# OpenMoteSTM-Border_DP83848CVV.net
KiCad netlist of a schematic drawn in Altium Designer
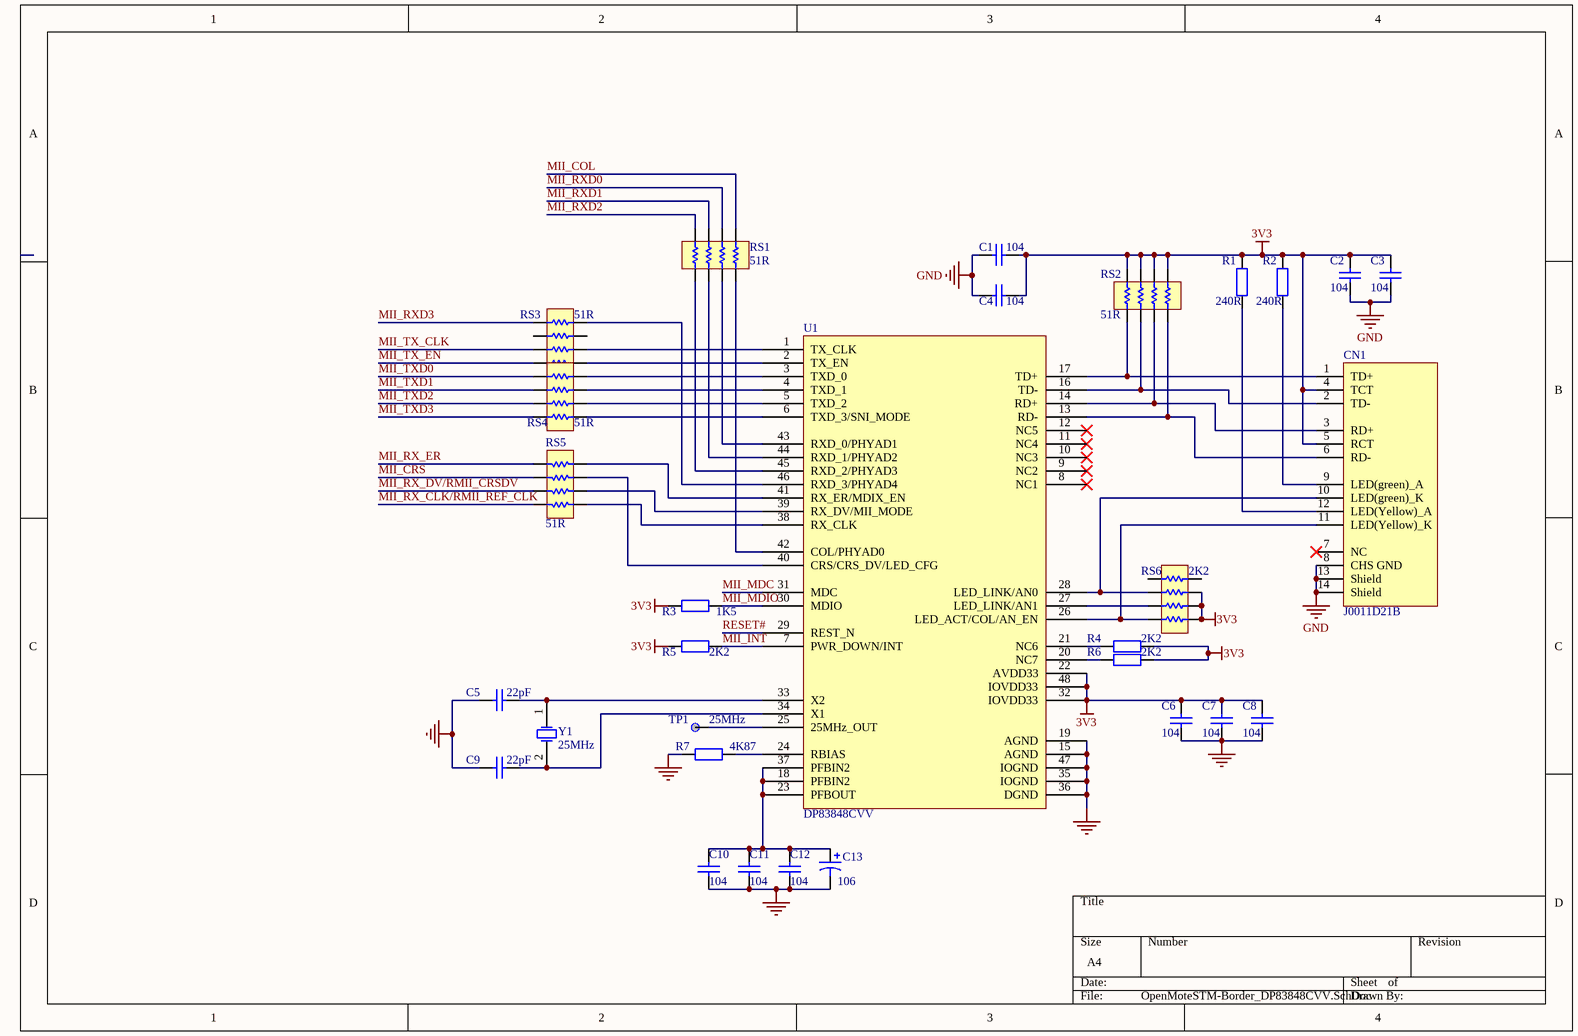
[diagram p0: OpenMoteSTM-Border_DP83848CVV.SchDoc]

(export (version "E")
  (design (tool "Eeschema 10.0.6"))
  (components
    (comp (ref "C1")
      (value "104")
      (footprint "0603")
      (description "Capacitor")
      (fields (field (name "Comment") "Cap") (field (name "PUBLISHER") "Altium Limited"))
      (libsource (lib "Miscellaneous Devices") (part "Cap"))
    )
    (comp (ref "C2")
      (value "104")
      (footprint "0603")
      (description "Capacitor")
      (fields (field (name "Comment") "Cap") (field (name "PUBLISHER") "Altium Limited"))
      (libsource (lib "Miscellaneous Devices") (part "Cap"))
    )
    (comp (ref "C3")
      (value "104")
      (footprint "0603")
      (description "Capacitor")
      (fields (field (name "Comment") "Cap") (field (name "PUBLISHER") "Altium Limited"))
      (libsource (lib "Miscellaneous Devices") (part "Cap"))
    )
    (comp (ref "C4")
      (value "104")
      (footprint "0603")
      (description "Capacitor")
      (fields (field (name "Comment") "Cap") (field (name "PUBLISHER") "Altium Limited"))
      (libsource (lib "Miscellaneous Devices") (part "Cap"))
    )
    (comp (ref "C5")
      (value "22pF")
      (footprint "0603")
      (description "Capacitor")
      (fields (field (name "Comment") "Cap") (field (name "PUBLISHER") "Altium Limited"))
      (libsource (lib "Miscellaneous Devices") (part "Cap"))
    )
    (comp (ref "C6")
      (value "104")
      (footprint "0603")
      (description "Capacitor")
      (fields (field (name "Comment") "Cap") (field (name "PUBLISHER") "Altium Limited"))
      (libsource (lib "Miscellaneous Devices") (part "Cap"))
    )
    (comp (ref "C7")
      (value "104")
      (footprint "0603")
      (description "Capacitor")
      (fields (field (name "Comment") "Cap") (field (name "PUBLISHER") "Altium Limited"))
      (libsource (lib "Miscellaneous Devices") (part "Cap"))
    )
    (comp (ref "C8")
      (value "104")
      (footprint "0603")
      (description "Capacitor")
      (fields (field (name "Comment") "Cap") (field (name "PUBLISHER") "Altium Limited"))
      (libsource (lib "Miscellaneous Devices") (part "Cap"))
    )
    (comp (ref "C9")
      (value "22pF")
      (footprint "0603")
      (description "Capacitor")
      (fields (field (name "Comment") "Cap") (field (name "PUBLISHER") "Altium Limited"))
      (libsource (lib "Miscellaneous Devices") (part "Cap"))
    )
    (comp (ref "C10")
      (value "104")
      (footprint "0603")
      (description "Capacitor")
      (fields (field (name "Comment") "Cap") (field (name "PUBLISHER") "Altium Limited"))
      (libsource (lib "Miscellaneous Devices") (part "Cap"))
    )
    (comp (ref "C11")
      (value "104")
      (footprint "0603")
      (description "Capacitor")
      (fields (field (name "Comment") "Cap") (field (name "PUBLISHER") "Altium Limited"))
      (libsource (lib "Miscellaneous Devices") (part "Cap"))
    )
    (comp (ref "C12")
      (value "104")
      (footprint "0603")
      (description "Capacitor")
      (fields (field (name "Comment") "Cap") (field (name "PUBLISHER") "Altium Limited"))
      (libsource (lib "Miscellaneous Devices") (part "Cap"))
    )
    (comp (ref "C13")
      (value "106")
      (footprint "1210")
      (description "Polarized Capacitor (Radial)")
      (fields (field (name "Comment") "Cap Pol1") (field (name "PUBLISHER") "Altium Limited"))
      (libsource (lib "Miscellaneous Devices") (part "Cap Pol1"))
    )
    (comp (ref "CN1") (value "J0011D21B") (footprint "RJ45") (libsource (lib "MB784") (part "J0011D21B")))
    (comp (ref "R1")
      (value "240R")
      (footprint "0603")
      (description "Resistor")
      (fields (field (name "Comment") "Res2") (field (name "PUBLISHER") "Altium Limited"))
      (libsource (lib "") (part "Res2_1"))
    )
    (comp (ref "R2")
      (value "240R")
      (footprint "0603")
      (description "Resistor")
      (fields (field (name "Comment") "Res2") (field (name "PUBLISHER") "Altium Limited"))
      (libsource (lib "") (part "Res2_1"))
    )
    (comp (ref "R3")
      (value "1K5")
      (footprint "0603")
      (description "Resistor")
      (fields (field (name "Comment") "Res2") (field (name "PUBLISHER") "Altium Limited"))
      (libsource (lib "Miscellaneous Devices") (part "Res2"))
    )
    (comp (ref "R4")
      (value "2K2")
      (footprint "0603")
      (description "Resistor")
      (fields (field (name "Comment") "Res2") (field (name "PUBLISHER") "Altium Limited"))
      (libsource (lib "Miscellaneous Devices") (part "Res2"))
    )
    (comp (ref "R5")
      (value "2K2")
      (footprint "0603")
      (description "Resistor")
      (fields (field (name "Comment") "Res2") (field (name "PUBLISHER") "Altium Limited"))
      (libsource (lib "Miscellaneous Devices") (part "Res2"))
    )
    (comp (ref "R6")
      (value "2K2")
      (footprint "0603")
      (description "Resistor")
      (fields (field (name "Comment") "Res2") (field (name "PUBLISHER") "Altium Limited"))
      (libsource (lib "Miscellaneous Devices") (part "Res2"))
    )
    (comp (ref "R7")
      (value "4K87")
      (footprint "0603")
      (description "Resistor")
      (fields (field (name "Comment") "Res2") (field (name "PUBLISHER") "Altium Limited"))
      (libsource (lib "Miscellaneous Devices") (part "Res2"))
    )
    (comp (ref "RS1") (value "51R") (footprint "RES-4B") (libsource (lib "") (part "Resister Array_2")))
    (comp (ref "RS2") (value "51R") (footprint "RES-4B") (libsource (lib "") (part "Resister Array_1")))
    (comp (ref "RS3") (value "51R") (footprint "RES-4B") (libsource (lib "MB784") (part "Resister Array")))
    (comp (ref "RS4") (value "51R") (footprint "RES-4B") (libsource (lib "MB784") (part "Resister Array")))
    (comp (ref "RS5") (value "51R") (footprint "RES-4B") (libsource (lib "") (part "Resister Array_1")))
    (comp (ref "RS6") (value "2K2") (footprint "RES-4B") (libsource (lib "MB784") (part "Resister Array")))
    (comp (ref "TP1") (value "25MHz") (footprint "TP") (libsource (lib "*") (part "TP")))
    (comp (ref "U1")
      (value "DP83848CVV")
      (footprint "DP83848CVV")
      (libsource (lib "OpenMoteSTM-Border") (part "DP83848CVV"))
    )
    (comp (ref "Y1")
      (value "25MHz")
      (footprint "XTAL")
      (description "Crystal Oscillator")
      (fields (field (name "PUBLISHER") "Altium Limited"))
      (libsource (lib "Miscellaneous Devices") (part "XTAL"))
    )
  )
  (nets
    (net (code "1") (name "/MII_COL") (class "Default")
      (node (ref "RS1") (pin "8") (pinfunction "8_8") (pintype "passive"))
    )
    (net (code "2") (name "/MII_CRS") (class "Default")
      (node (ref "RS5") (pin "4") (pinfunction "4_4") (pintype "passive"))
    )
    (net (code "3") (name "/MII_INT") (class "Default")
      (node (ref "R5") (pin "2") (pinfunction "2_2") (pintype "passive"))
      (node (ref "U1") (pin "7") (pinfunction "PWR_DOWN/INT_7") (pintype "passive"))
    )
    (net (code "4") (name "/MII_MDC") (class "Default")
      (node (ref "U1") (pin "31") (pinfunction "MDC_31") (pintype "passive"))
    )
    (net (code "5") (name "/MII_MDIO") (class "Default")
      (node (ref "R3") (pin "2") (pinfunction "2_2") (pintype "passive"))
      (node (ref "U1") (pin "30") (pinfunction "MDIO_30") (pintype "passive"))
    )
    (net (code "6") (name "/MII_RXD0") (class "Default")
      (node (ref "RS1") (pin "6") (pinfunction "6_6") (pintype "passive"))
    )
    (net (code "7") (name "/MII_RXD1") (class "Default")
      (node (ref "RS1") (pin "4") (pinfunction "4_4") (pintype "passive"))
    )
    (net (code "8") (name "/MII_RXD2") (class "Default")
      (node (ref "RS1") (pin "2") (pinfunction "2_2") (pintype "passive"))
    )
    (net (code "9") (name "/MII_RXD3") (class "Default")
      (node (ref "RS3") (pin "1") (pinfunction "1_1") (pintype "passive"))
    )
    (net (code "10") (name "/MII_RX_CLK{slash}RMII_REF_CLK") (class "Default")
      (node (ref "RS5") (pin "8") (pinfunction "8_8") (pintype "passive"))
    )
    (net (code "11") (name "/MII_RX_DV{slash}RMII_CRSDV") (class "Default")
      (node (ref "RS5") (pin "6") (pinfunction "6_6") (pintype "passive"))
    )
    (net (code "12") (name "/MII_RX_ER") (class "Default")
      (node (ref "RS5") (pin "2") (pinfunction "2_2") (pintype "passive"))
    )
    (net (code "13") (name "/MII_TXD0") (class "Default")
      (node (ref "RS4") (pin "1") (pinfunction "1_1") (pintype "passive"))
    )
    (net (code "14") (name "/MII_TXD1") (class "Default")
      (node (ref "RS4") (pin "3") (pinfunction "3_3") (pintype "passive"))
    )
    (net (code "15") (name "/MII_TXD2") (class "Default")
      (node (ref "RS4") (pin "5") (pinfunction "5_5") (pintype "passive"))
    )
    (net (code "16") (name "/MII_TXD3") (class "Default")
      (node (ref "RS4") (pin "7") (pinfunction "7_7") (pintype "passive"))
    )
    (net (code "17") (name "/MII_TX_CLK") (class "Default")
      (node (ref "RS3") (pin "5") (pinfunction "5_5") (pintype "passive"))
    )
    (net (code "18") (name "/MII_TX_EN") (class "Default")
      (node (ref "RS3") (pin "7") (pinfunction "7_7") (pintype "passive"))
    )
    (net (code "19") (name "/RESET#") (class "Default")
      (node (ref "U1") (pin "29") (pinfunction "REST_N_29") (pintype "passive"))
    )
    (net (code "20") (name "3V3") (class "Default")
      (node (ref "C1") (pin "2") (pinfunction "2_2") (pintype "passive"))
      (node (ref "C2") (pin "2") (pinfunction "2_2") (pintype "passive"))
      (node (ref "C3") (pin "2") (pinfunction "2_2") (pintype "passive"))
      (node (ref "C4") (pin "2") (pinfunction "2_2") (pintype "passive"))
      (node (ref "C6") (pin "2") (pinfunction "2_2") (pintype "passive"))
      (node (ref "C7") (pin "2") (pinfunction "2_2") (pintype "passive"))
      (node (ref "C8") (pin "2") (pinfunction "2_2") (pintype "passive"))
      (node (ref "CN1") (pin "4") (pinfunction "TCT_4") (pintype "passive"))
      (node (ref "CN1") (pin "5") (pinfunction "RCT_5") (pintype "passive"))
      (node (ref "R1") (pin "2") (pinfunction "2_2") (pintype "passive"))
      (node (ref "R2") (pin "2") (pinfunction "2_2") (pintype "passive"))
      (node (ref "R3") (pin "1") (pinfunction "1_1") (pintype "passive"))
      (node (ref "R4") (pin "2") (pinfunction "2_2") (pintype "passive"))
      (node (ref "R5") (pin "1") (pinfunction "1_1") (pintype "passive"))
      (node (ref "R6") (pin "2") (pinfunction "2_2") (pintype "passive"))
      (node (ref "RS2") (pin "1") (pinfunction "1_1") (pintype "passive"))
      (node (ref "RS2") (pin "3") (pinfunction "3_3") (pintype "passive"))
      (node (ref "RS2") (pin "5") (pinfunction "5_5") (pintype "passive"))
      (node (ref "RS2") (pin "7") (pinfunction "7_7") (pintype "passive"))
      (node (ref "RS6") (pin "4") (pinfunction "4_4") (pintype "passive"))
      (node (ref "RS6") (pin "6") (pinfunction "6_6") (pintype "passive"))
      (node (ref "RS6") (pin "8") (pinfunction "8_8") (pintype "passive"))
      (node (ref "U1") (pin "22") (pinfunction "AVDD33_22") (pintype "passive"))
      (node (ref "U1") (pin "32") (pinfunction "IOVDD33_32") (pintype "passive"))
      (node (ref "U1") (pin "48") (pinfunction "IOVDD33_48") (pintype "passive"))
    )
    (net (code "21") (name "GND") (class "Default")
      (node (ref "C1") (pin "1") (pinfunction "1_1") (pintype "passive"))
      (node (ref "C10") (pin "1") (pinfunction "1_1") (pintype "passive"))
      (node (ref "C11") (pin "1") (pinfunction "1_1") (pintype "passive"))
      (node (ref "C12") (pin "1") (pinfunction "1_1") (pintype "passive"))
      (node (ref "C13") (pin "2") (pinfunction "2_2") (pintype "passive"))
      (node (ref "C2") (pin "1") (pinfunction "1_1") (pintype "passive"))
      (node (ref "C3") (pin "1") (pinfunction "1_1") (pintype "passive"))
      (node (ref "C4") (pin "1") (pinfunction "1_1") (pintype "passive"))
      (node (ref "C5") (pin "1") (pinfunction "1_1") (pintype "passive"))
      (node (ref "C6") (pin "1") (pinfunction "1_1") (pintype "passive"))
      (node (ref "C7") (pin "1") (pinfunction "1_1") (pintype "passive"))
      (node (ref "C8") (pin "1") (pinfunction "1_1") (pintype "passive"))
      (node (ref "C9") (pin "1") (pinfunction "1_1") (pintype "passive"))
      (node (ref "CN1") (pin "13") (pinfunction "Shield_13") (pintype "passive"))
      (node (ref "CN1") (pin "14") (pinfunction "Shield_14") (pintype "passive"))
      (node (ref "CN1") (pin "8") (pinfunction "CHS_GND_8") (pintype "passive"))
      (node (ref "R7") (pin "1") (pinfunction "1_1") (pintype "passive"))
      (node (ref "U1") (pin "15") (pinfunction "AGND_15") (pintype "passive"))
      (node (ref "U1") (pin "19") (pinfunction "AGND_19") (pintype "passive"))
      (node (ref "U1") (pin "35") (pinfunction "IOGND_35") (pintype "passive"))
      (node (ref "U1") (pin "36") (pinfunction "DGND_36") (pintype "passive"))
      (node (ref "U1") (pin "47") (pinfunction "IOGND_47") (pintype "passive"))
    )
    (net (code "22") (name "Net-(CN1-LED(Yellow)_A)") (class "Default")
      (node (ref "CN1") (pin "12") (pinfunction "LED(Yellow)_A_12") (pintype "passive"))
      (node (ref "R1") (pin "1") (pinfunction "1_1") (pintype "passive"))
    )
    (net (code "23") (name "Net-(CN1-LED(Yellow)_K)") (class "Default")
      (node (ref "CN1") (pin "11") (pinfunction "LED(Yellow)_K_11") (pintype "passive"))
      (node (ref "RS6") (pin "7") (pinfunction "7_7") (pintype "passive"))
      (node (ref "U1") (pin "26") (pinfunction "LED_ACT/COL/AN_EN_26") (pintype "passive"))
    )
    (net (code "24") (name "Net-(CN1-LED(green)_A)") (class "Default")
      (node (ref "CN1") (pin "9") (pinfunction "LED(green)_A_9") (pintype "passive"))
      (node (ref "R2") (pin "1") (pinfunction "1_1") (pintype "passive"))
    )
    (net (code "25") (name "Net-(CN1-LED(green)_K)") (class "Default")
      (node (ref "CN1") (pin "10") (pinfunction "LED(green)_K_10") (pintype "passive"))
      (node (ref "RS6") (pin "3") (pinfunction "3_3") (pintype "passive"))
      (node (ref "U1") (pin "28") (pinfunction "LED_LINK/AN0_28") (pintype "passive"))
    )
    (net (code "26") (name "Net-(CN1-RD+)") (class "Default")
      (node (ref "CN1") (pin "3") (pinfunction "RD+_3") (pintype "passive"))
      (node (ref "RS2") (pin "4") (pinfunction "4_4") (pintype "passive"))
      (node (ref "U1") (pin "14") (pinfunction "RD+_14") (pintype "passive"))
    )
    (net (code "27") (name "Net-(CN1-RD-)") (class "Default")
      (node (ref "CN1") (pin "6") (pinfunction "RD-_6") (pintype "passive"))
      (node (ref "RS2") (pin "2") (pinfunction "2_2") (pintype "passive"))
      (node (ref "U1") (pin "13") (pinfunction "RD-_13") (pintype "passive"))
    )
    (net (code "28") (name "Net-(CN1-TD+)") (class "Default")
      (node (ref "CN1") (pin "1") (pinfunction "TD+_1") (pintype "passive"))
      (node (ref "RS2") (pin "8") (pinfunction "8_8") (pintype "passive"))
      (node (ref "U1") (pin "17") (pinfunction "TD+_17") (pintype "passive"))
    )
    (net (code "29") (name "Net-(CN1-TD-)") (class "Default")
      (node (ref "CN1") (pin "2") (pinfunction "TD-_2") (pintype "passive"))
      (node (ref "RS2") (pin "6") (pinfunction "6_6") (pintype "passive"))
      (node (ref "U1") (pin "16") (pinfunction "TD-_16") (pintype "passive"))
    )
    (net (code "30") (name "Net-(U1-25MHz_OUT)") (class "Default")
      (node (ref "TP1") (pin "1") (pinfunction "1_1") (pintype "passive"))
      (node (ref "U1") (pin "25") (pinfunction "25MHz_OUT_25") (pintype "passive"))
    )
    (net (code "31") (name "Net-(U1-COL{slash}PHYAD0)") (class "Default")
      (node (ref "RS1") (pin "7") (pinfunction "7_7") (pintype "passive"))
      (node (ref "U1") (pin "42") (pinfunction "COL/PHYAD0_42") (pintype "passive"))
    )
    (net (code "32") (name "Net-(U1-CRS{slash}CRS_DV{slash}LED_CFG)") (class "Default")
      (node (ref "RS5") (pin "3") (pinfunction "3_3") (pintype "passive"))
      (node (ref "U1") (pin "40") (pinfunction "CRS/CRS_DV/LED_CFG_40") (pintype "passive"))
    )
    (net (code "33") (name "Net-(U1-LED_LINK{slash}AN1)") (class "Default")
      (node (ref "RS6") (pin "5") (pinfunction "5_5") (pintype "passive"))
      (node (ref "U1") (pin "27") (pinfunction "LED_LINK/AN1_27") (pintype "passive"))
    )
    (net (code "34") (name "Net-(U1-NC6)") (class "Default")
      (node (ref "R4") (pin "1") (pinfunction "1_1") (pintype "passive"))
      (node (ref "U1") (pin "21") (pinfunction "NC6_21") (pintype "passive"))
    )
    (net (code "35") (name "Net-(U1-NC7)") (class "Default")
      (node (ref "R6") (pin "1") (pinfunction "1_1") (pintype "passive"))
      (node (ref "U1") (pin "20") (pinfunction "NC7_20") (pintype "passive"))
    )
    (net (code "36") (name "Net-(U1-PFBOUT)") (class "Default")
      (node (ref "C10") (pin "2") (pinfunction "2_2") (pintype "passive"))
      (node (ref "C11") (pin "2") (pinfunction "2_2") (pintype "passive"))
      (node (ref "C12") (pin "2") (pinfunction "2_2") (pintype "passive"))
      (node (ref "C13") (pin "1") (pinfunction "1_1") (pintype "passive"))
      (node (ref "U1") (pin "18") (pinfunction "PFBIN2_18") (pintype "passive"))
      (node (ref "U1") (pin "23") (pinfunction "PFBOUT_23") (pintype "passive"))
      (node (ref "U1") (pin "37") (pinfunction "PFBIN2_37") (pintype "passive"))
    )
    (net (code "37") (name "Net-(U1-RBIAS)") (class "Default")
      (node (ref "R7") (pin "2") (pinfunction "2_2") (pintype "passive"))
      (node (ref "U1") (pin "24") (pinfunction "RBIAS_24") (pintype "passive"))
    )
    (net (code "38") (name "Net-(U1-RXD_0{slash}PHYAD1)") (class "Default")
      (node (ref "RS1") (pin "5") (pinfunction "5_5") (pintype "passive"))
      (node (ref "U1") (pin "43") (pinfunction "RXD_0/PHYAD1_43") (pintype "passive"))
    )
    (net (code "39") (name "Net-(U1-RXD_1{slash}PHYAD2)") (class "Default")
      (node (ref "RS1") (pin "3") (pinfunction "3_3") (pintype "passive"))
      (node (ref "U1") (pin "44") (pinfunction "RXD_1/PHYAD2_44") (pintype "passive"))
    )
    (net (code "40") (name "Net-(U1-RXD_2{slash}PHYAD3)") (class "Default")
      (node (ref "RS1") (pin "1") (pinfunction "1_1") (pintype "passive"))
      (node (ref "U1") (pin "45") (pinfunction "RXD_2/PHYAD3_45") (pintype "passive"))
    )
    (net (code "41") (name "Net-(U1-RXD_3{slash}PHYAD4)") (class "Default")
      (node (ref "RS3") (pin "2") (pinfunction "2_2") (pintype "passive"))
      (node (ref "U1") (pin "46") (pinfunction "RXD_3/PHYAD4_46") (pintype "passive"))
    )
    (net (code "42") (name "Net-(U1-RX_CLK)") (class "Default")
      (node (ref "RS5") (pin "7") (pinfunction "7_7") (pintype "passive"))
      (node (ref "U1") (pin "38") (pinfunction "RX_CLK_38") (pintype "passive"))
    )
    (net (code "43") (name "Net-(U1-RX_DV{slash}MII_MODE)") (class "Default")
      (node (ref "RS5") (pin "5") (pinfunction "5_5") (pintype "passive"))
      (node (ref "U1") (pin "39") (pinfunction "RX_DV/MII_MODE_39") (pintype "passive"))
    )
    (net (code "44") (name "Net-(U1-RX_ER{slash}MDIX_EN)") (class "Default")
      (node (ref "RS5") (pin "1") (pinfunction "1_1") (pintype "passive"))
      (node (ref "U1") (pin "41") (pinfunction "RX_ER/MDIX_EN_41") (pintype "passive"))
    )
    (net (code "45") (name "Net-(U1-TXD_0)") (class "Default")
      (node (ref "RS4") (pin "2") (pinfunction "2_2") (pintype "passive"))
      (node (ref "U1") (pin "3") (pinfunction "TXD_0_3") (pintype "passive"))
    )
    (net (code "46") (name "Net-(U1-TXD_1)") (class "Default")
      (node (ref "RS4") (pin "4") (pinfunction "4_4") (pintype "passive"))
      (node (ref "U1") (pin "4") (pinfunction "TXD_1_4") (pintype "passive"))
    )
    (net (code "47") (name "Net-(U1-TXD_2)") (class "Default")
      (node (ref "RS4") (pin "6") (pinfunction "6_6") (pintype "passive"))
      (node (ref "U1") (pin "5") (pinfunction "TXD_2_5") (pintype "passive"))
    )
    (net (code "48") (name "Net-(U1-TXD_3{slash}SNI_MODE)") (class "Default")
      (node (ref "RS4") (pin "8") (pinfunction "8_8") (pintype "passive"))
      (node (ref "U1") (pin "6") (pinfunction "TXD_3/SNI_MODE_6") (pintype "passive"))
    )
    (net (code "49") (name "Net-(U1-TX_CLK)") (class "Default")
      (node (ref "RS3") (pin "6") (pinfunction "6_6") (pintype "passive"))
      (node (ref "U1") (pin "1") (pinfunction "TX_CLK_1") (pintype "passive"))
    )
    (net (code "50") (name "Net-(U1-TX_EN)") (class "Default")
      (node (ref "RS3") (pin "8") (pinfunction "8_8") (pintype "passive"))
      (node (ref "U1") (pin "2") (pinfunction "TX_EN_2") (pintype "passive"))
    )
    (net (code "51") (name "Net-(U1-X1)") (class "Default")
      (node (ref "C9") (pin "2") (pinfunction "2_2") (pintype "passive"))
      (node (ref "U1") (pin "34") (pinfunction "X1_34") (pintype "passive"))
      (node (ref "Y1") (pin "2") (pinfunction "OSC2_2") (pintype "passive"))
    )
    (net (code "52") (name "Net-(U1-X2)") (class "Default")
      (node (ref "C5") (pin "2") (pinfunction "2_2") (pintype "passive"))
      (node (ref "U1") (pin "33") (pinfunction "X2_33") (pintype "passive"))
      (node (ref "Y1") (pin "1") (pinfunction "OSC1_1") (pintype "passive"))
    )
    (net (code "53") (name "unconnected-(CN1-NC-Pad7)") (class "Default")
      (node (ref "CN1") (pin "7") (pinfunction "NC_7") (pintype "passive+no_connect"))
    )
    (net (code "54") (name "unconnected-(RS3-Pad3)") (class "Default")
      (node (ref "RS3") (pin "3") (pinfunction "3_3") (pintype "passive"))
    )
    (net (code "55") (name "unconnected-(RS3-Pad4)") (class "Default")
      (node (ref "RS3") (pin "4") (pinfunction "4_4") (pintype "passive"))
    )
    (net (code "56") (name "unconnected-(RS6-Pad1)") (class "Default")
      (node (ref "RS6") (pin "1") (pinfunction "1_1") (pintype "passive"))
    )
    (net (code "57") (name "unconnected-(RS6-Pad2)") (class "Default")
      (node (ref "RS6") (pin "2") (pinfunction "2_2") (pintype "passive"))
    )
    (net (code "58") (name "unconnected-(U1-NC1-Pad8)") (class "Default")
      (node (ref "U1") (pin "8") (pinfunction "NC1_8") (pintype "passive+no_connect"))
    )
    (net (code "59") (name "unconnected-(U1-NC2-Pad9)") (class "Default")
      (node (ref "U1") (pin "9") (pinfunction "NC2_9") (pintype "passive+no_connect"))
    )
    (net (code "60") (name "unconnected-(U1-NC3-Pad10)") (class "Default")
      (node (ref "U1") (pin "10") (pinfunction "NC3_10") (pintype "passive+no_connect"))
    )
    (net (code "61") (name "unconnected-(U1-NC4-Pad11)") (class "Default")
      (node (ref "U1") (pin "11") (pinfunction "NC4_11") (pintype "passive+no_connect"))
    )
    (net (code "62") (name "unconnected-(U1-NC5-Pad12)") (class "Default")
      (node (ref "U1") (pin "12") (pinfunction "NC5_12") (pintype "passive+no_connect"))
    )
  )
)
